# Small_e-PaperShield_v2_1.net
KiCad netlist of a schematic drawn in EAGLE
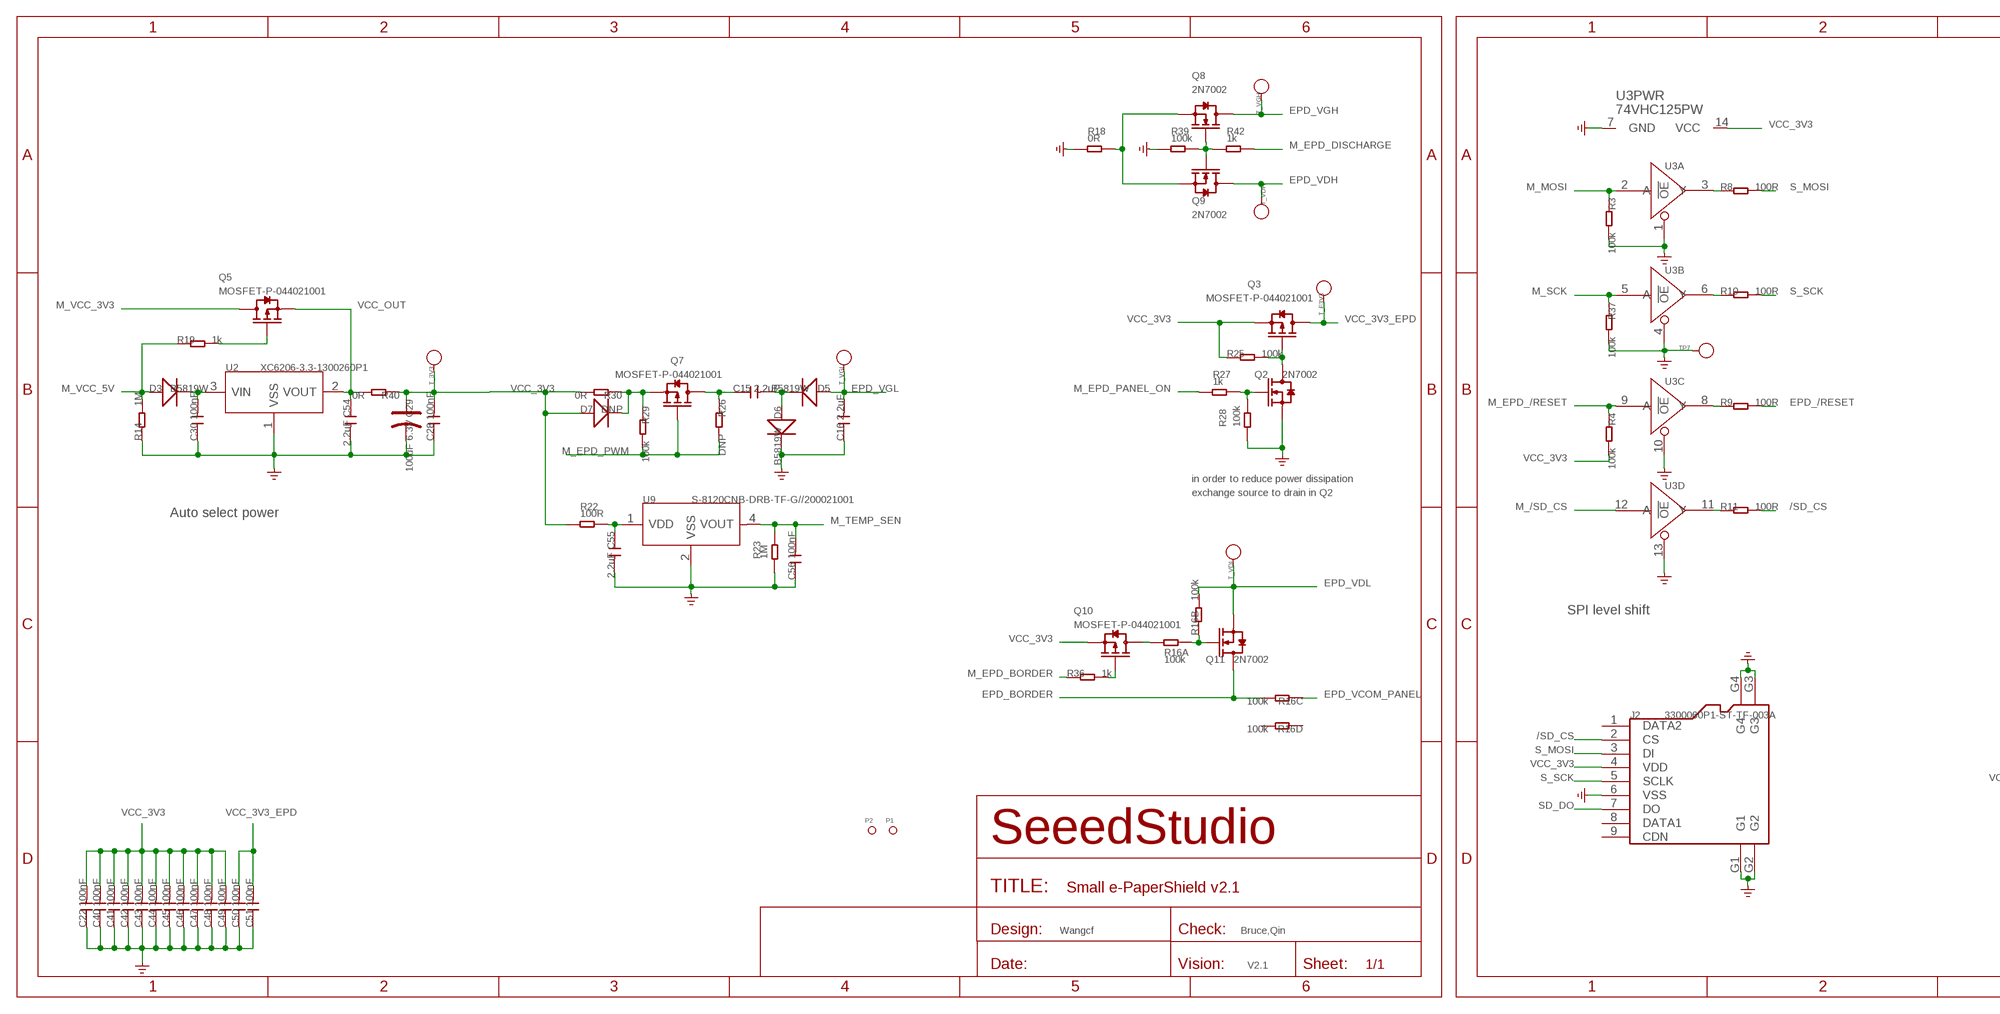
[diagram p0: schematic, sheet 1, part 1 of 2]
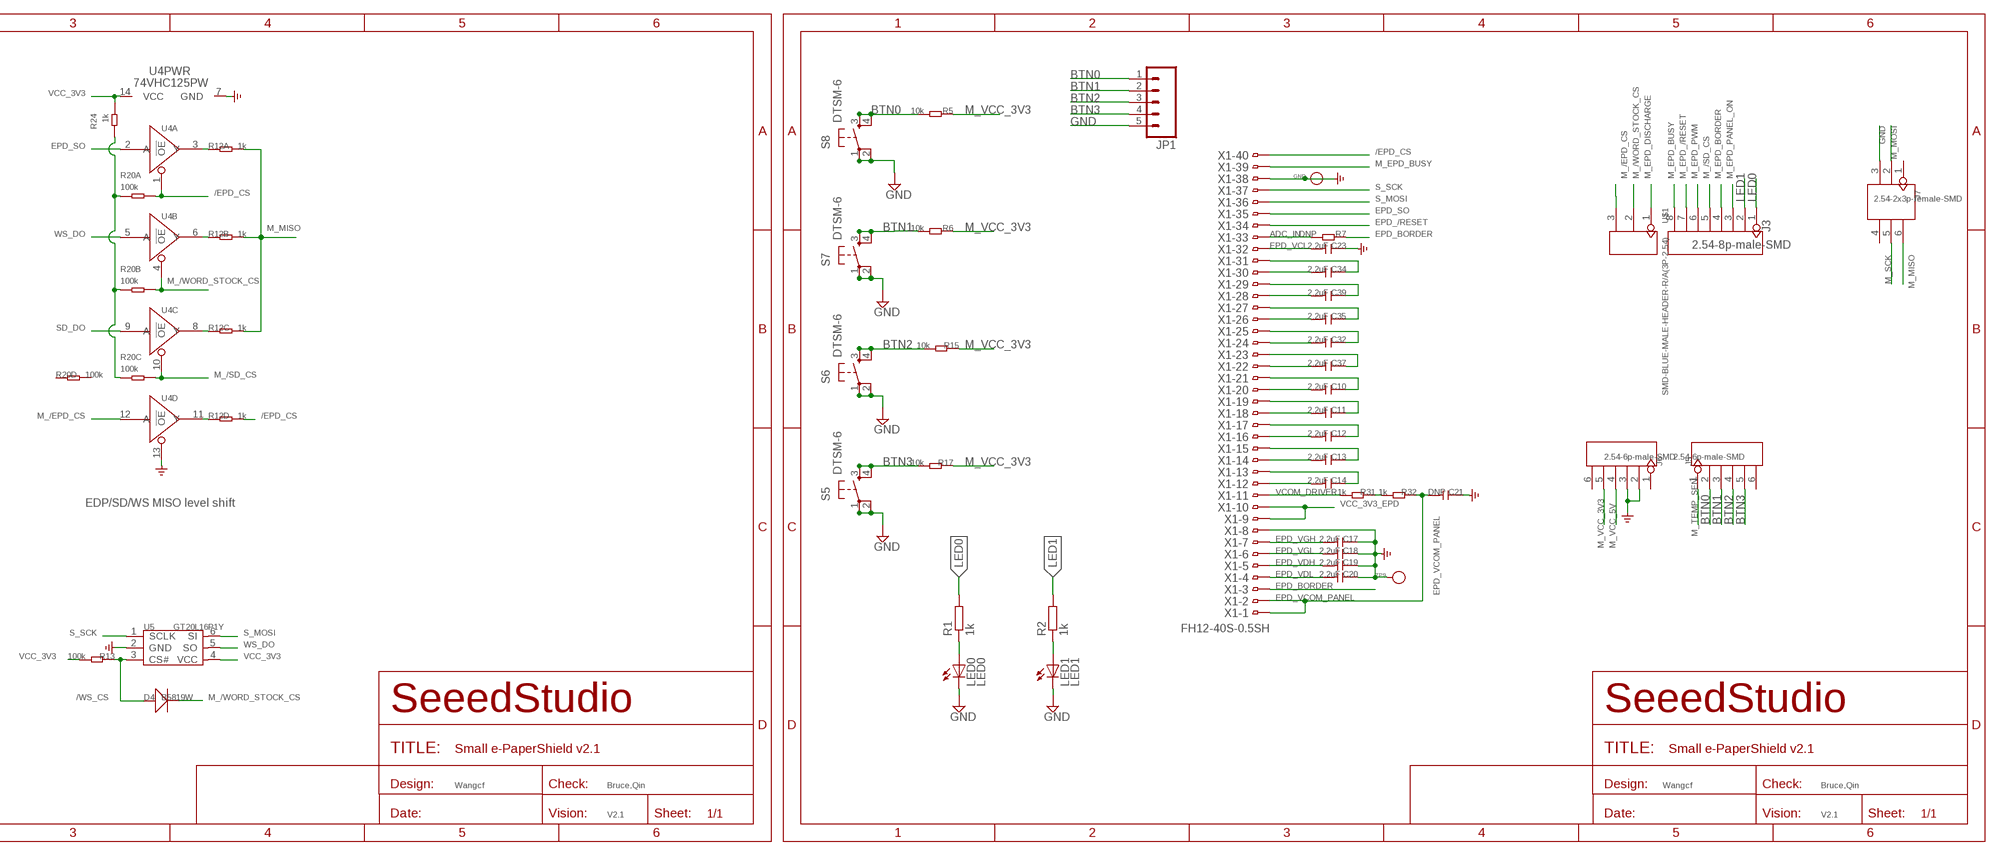
[diagram p1: schematic, sheet 1, part 2 of 2]

(export (version "E")
  (design (tool "Eeschema 10.0.6"))
  (components
    (comp (ref "C10")
      (value "2.2uF")
      (footprint "eagle-import:C0805")
      (libsource (lib "eagle-import") (part "C-0805"))
    )
    (comp (ref "C11")
      (value "2.2uF")
      (footprint "eagle-import:C0805")
      (libsource (lib "eagle-import") (part "C-0805"))
    )
    (comp (ref "C12")
      (value "2.2uF")
      (footprint "eagle-import:C0805")
      (libsource (lib "eagle-import") (part "C-0805"))
    )
    (comp (ref "C13")
      (value "2.2uF")
      (footprint "eagle-import:C0805")
      (libsource (lib "eagle-import") (part "C-0805"))
    )
    (comp (ref "C14")
      (value "2.2uF")
      (footprint "eagle-import:C0805")
      (libsource (lib "eagle-import") (part "C-0805"))
    )
    (comp (ref "C15")
      (value "2.2uF")
      (footprint "eagle-import:C0805")
      (libsource (lib "eagle-import") (part "C-0805"))
    )
    (comp (ref "C16")
      (value "2.2uF")
      (footprint "eagle-import:C0805")
      (libsource (lib "eagle-import") (part "C-0805"))
    )
    (comp (ref "C17")
      (value "2.2uF")
      (footprint "eagle-import:C0805")
      (libsource (lib "eagle-import") (part "C-0805"))
    )
    (comp (ref "C18")
      (value "2.2uF")
      (footprint "eagle-import:C0805")
      (libsource (lib "eagle-import") (part "C-0805"))
    )
    (comp (ref "C19")
      (value "2.2uF")
      (footprint "eagle-import:C0805")
      (libsource (lib "eagle-import") (part "C-0805"))
    )
    (comp (ref "C20")
      (value "2.2uF")
      (footprint "eagle-import:C0805")
      (libsource (lib "eagle-import") (part "C-0805"))
    )
    (comp (ref "C21")
      (value "DNP")
      (footprint "eagle-import:C0805")
      (libsource (lib "eagle-import") (part "C-0805"))
    )
    (comp (ref "C22")
      (value "100nF")
      (footprint "eagle-import:C0603")
      (libsource (lib "eagle-import") (part "C-0603"))
    )
    (comp (ref "C23")
      (value "2.2uF")
      (footprint "eagle-import:C0805")
      (libsource (lib "eagle-import") (part "C-0805"))
    )
    (comp (ref "C28")
      (value "100nF")
      (footprint "eagle-import:C0603")
      (libsource (lib "eagle-import") (part "C-0603"))
    )
    (comp (ref "C29")
      (value "100uF 6.3V")
      (footprint "eagle-import:AVX-B")
      (libsource (lib "eagle-import") (part "CAP-AVX-B"))
    )
    (comp (ref "C30")
      (value "100nF")
      (footprint "eagle-import:C0603")
      (libsource (lib "eagle-import") (part "C-0603"))
    )
    (comp (ref "C32")
      (value "2.2uF")
      (footprint "eagle-import:C0805")
      (libsource (lib "eagle-import") (part "C-0805"))
    )
    (comp (ref "C34")
      (value "2.2uF")
      (footprint "eagle-import:C0805")
      (libsource (lib "eagle-import") (part "C-0805"))
    )
    (comp (ref "C35")
      (value "2.2uF")
      (footprint "eagle-import:C0805")
      (libsource (lib "eagle-import") (part "C-0805"))
    )
    (comp (ref "C37")
      (value "2.2uF")
      (footprint "eagle-import:C0805")
      (libsource (lib "eagle-import") (part "C-0805"))
    )
    (comp (ref "C39")
      (value "2.2uF")
      (footprint "eagle-import:C0805")
      (libsource (lib "eagle-import") (part "C-0805"))
    )
    (comp (ref "C40")
      (value "100nF")
      (footprint "eagle-import:C0603")
      (libsource (lib "eagle-import") (part "C-0603"))
    )
    (comp (ref "C41")
      (value "100nF")
      (footprint "eagle-import:C0603")
      (libsource (lib "eagle-import") (part "C-0603"))
    )
    (comp (ref "C42")
      (value "100nF")
      (footprint "eagle-import:C0603")
      (libsource (lib "eagle-import") (part "C-0603"))
    )
    (comp (ref "C43")
      (value "100nF")
      (footprint "eagle-import:C0603")
      (libsource (lib "eagle-import") (part "C-0603"))
    )
    (comp (ref "C44")
      (value "100nF")
      (footprint "eagle-import:C0603")
      (libsource (lib "eagle-import") (part "C-0603"))
    )
    (comp (ref "C45")
      (value "100nF")
      (footprint "eagle-import:C0603")
      (libsource (lib "eagle-import") (part "C-0603"))
    )
    (comp (ref "C46")
      (value "100nF")
      (footprint "eagle-import:C0603")
      (libsource (lib "eagle-import") (part "C-0603"))
    )
    (comp (ref "C47")
      (value "100nF")
      (footprint "eagle-import:C0603")
      (libsource (lib "eagle-import") (part "C-0603"))
    )
    (comp (ref "C48")
      (value "100nF")
      (footprint "eagle-import:C0603")
      (libsource (lib "eagle-import") (part "C-0603"))
    )
    (comp (ref "C49")
      (value "100nF")
      (footprint "eagle-import:C0603")
      (libsource (lib "eagle-import") (part "C-0603"))
    )
    (comp (ref "C50")
      (value "100nF")
      (footprint "eagle-import:C0603")
      (libsource (lib "eagle-import") (part "C-0603"))
    )
    (comp (ref "C51")
      (value "100nF")
      (footprint "eagle-import:C0603")
      (libsource (lib "eagle-import") (part "C-0603"))
    )
    (comp (ref "C54")
      (value "2.2uF")
      (footprint "eagle-import:C0805")
      (libsource (lib "eagle-import") (part "C-0805"))
    )
    (comp (ref "C55")
      (value "2.2uF")
      (footprint "eagle-import:C0805")
      (libsource (lib "eagle-import") (part "C-0805"))
    )
    (comp (ref "C56")
      (value "100nF")
      (footprint "eagle-import:C0603")
      (libsource (lib "eagle-import") (part "C-0603"))
    )
    (comp (ref "D3")
      (value "B5819W")
      (footprint "eagle-import:SOD123")
      (libsource (lib "eagle-import") (part "D'1206'"))
    )
    (comp (ref "D4")
      (value "B5819W")
      (footprint "eagle-import:SOD123")
      (libsource (lib "eagle-import") (part "D'1206'"))
    )
    (comp (ref "D5")
      (value "B5819W")
      (footprint "eagle-import:SOD123")
      (libsource (lib "eagle-import") (part "D'1206'"))
    )
    (comp (ref "D6")
      (value "B5819W")
      (footprint "eagle-import:SOD123")
      (libsource (lib "eagle-import") (part "D'1206'"))
    )
    (comp (ref "D7")
      (value "DNP")
      (footprint "eagle-import:SOD123")
      (libsource (lib "eagle-import") (part "D'1206'"))
    )
    (comp (ref "GND")
      (value "PAD-TEST-POINT'3535'")
      (footprint "eagle-import:TP_3535")
      (fields (field (name "PARTNO") "DNP"))
      (libsource (lib "eagle-import") (part "PAD-TEST-POINT'3535'"))
    )
    (comp (ref "J2")
      (value "3300060P1-ST-TF-003A")
      (footprint "eagle-import:9P-SMD-W_-RING")
      (libsource (lib "eagle-import") (part "3300060P1-ST-TF-003A"))
    )
    (comp (ref "J3")
      (value "2.54-8p-male-SMD")
      (footprint "eagle-import:8P-2.54-SMD")
      (libsource (lib "eagle-import") (part "HEADER-8P-2.54-SMD"))
    )
    (comp (ref "J5")
      (value "2.54-6p-male-SMD")
      (footprint "eagle-import:6P-2.54-SMD")
      (libsource (lib "eagle-import") (part "HEADER-6P-SMD"))
    )
    (comp (ref "J6")
      (value "2.54-6p-male-SMD")
      (footprint "eagle-import:6P-2.54-SMD")
      (libsource (lib "eagle-import") (part "HEADER-6P-SMD"))
    )
    (comp (ref "J7")
      (value "2.54-2x3p-female-SMD")
      (footprint "eagle-import:2X3P-2.54-SMD")
      (libsource (lib "eagle-import") (part "HEADER-2X3P-SMD"))
    )
    (comp (ref "JP1")
      (value "M05PTH_LONGPADS")
      (footprint "eagle-import:1X05_LONGPADS")
      (libsource (lib "eagle-import") (part "M05PTH_LONGPADS"))
    )
    (comp (ref "LED0")
      (value "LED0")
      (footprint "eagle-import:CHIPLED_0603")
      (libsource (lib "eagle-import") (part "LEDCHIPLED_0603"))
    )
    (comp (ref "LED1")
      (value "LED1")
      (footprint "eagle-import:CHIPLED_0603")
      (libsource (lib "eagle-import") (part "LEDCHIPLED_0603"))
    )
    (comp (ref "P1")
      (value "PAD-MARK")
      (footprint "eagle-import:ROUND-MARK-1.0")
      (fields (field (name "PARTNO") "DNP"))
      (libsource (lib "eagle-import") (part "PAD-MARK"))
    )
    (comp (ref "P2")
      (value "PAD-MARK")
      (footprint "eagle-import:ROUND-MARK-1.0")
      (fields (field (name "PARTNO") "DNP"))
      (libsource (lib "eagle-import") (part "PAD-MARK"))
    )
    (comp (ref "Q2")
      (value "2N7002")
      (footprint "eagle-import:SOT23")
      (libsource (lib "eagle-import") (part "MOSFET-N'SOT23'"))
    )
    (comp (ref "Q3")
      (value "MOSFET-P-044021001")
      (footprint "eagle-import:SOT23")
      (libsource (lib "eagle-import") (part "MOSFET-P-044021001"))
    )
    (comp (ref "Q5")
      (value "MOSFET-P-044021001")
      (footprint "eagle-import:SOT23")
      (libsource (lib "eagle-import") (part "MOSFET-P-044021001"))
    )
    (comp (ref "Q7")
      (value "MOSFET-P-044021001")
      (footprint "eagle-import:SOT23")
      (libsource (lib "eagle-import") (part "MOSFET-P-044021001"))
    )
    (comp (ref "Q8")
      (value "2N7002")
      (footprint "eagle-import:SOT23")
      (libsource (lib "eagle-import") (part "MOSFET-N'SOT23'"))
    )
    (comp (ref "Q9")
      (value "2N7002")
      (footprint "eagle-import:SOT23")
      (libsource (lib "eagle-import") (part "MOSFET-N'SOT23'"))
    )
    (comp (ref "Q10")
      (value "MOSFET-P-044021001")
      (footprint "eagle-import:SOT23")
      (libsource (lib "eagle-import") (part "MOSFET-P-044021001"))
    )
    (comp (ref "Q11")
      (value "2N7002")
      (footprint "eagle-import:SOT23")
      (libsource (lib "eagle-import") (part "MOSFET-N'SOT23'"))
    )
    (comp (ref "R1")
      (value "1k")
      (footprint "eagle-import:R0603")
      (libsource (lib "eagle-import") (part "R-EU_R0603"))
    )
    (comp (ref "R2")
      (value "1k")
      (footprint "eagle-import:R0603")
      (libsource (lib "eagle-import") (part "R-EU_R0603"))
    )
    (comp (ref "R3")
      (value "100k")
      (footprint "eagle-import:R0603")
      (libsource (lib "eagle-import") (part "R-0603"))
    )
    (comp (ref "R4")
      (value "100k")
      (footprint "eagle-import:R0603")
      (libsource (lib "eagle-import") (part "R-0603"))
    )
    (comp (ref "R5")
      (value "10k")
      (footprint "eagle-import:R0603")
      (libsource (lib "eagle-import") (part "R-0603"))
    )
    (comp (ref "R6")
      (value "10k")
      (footprint "eagle-import:R0603")
      (libsource (lib "eagle-import") (part "R-0603"))
    )
    (comp (ref "R7")
      (value "DNP")
      (footprint "eagle-import:R0603")
      (libsource (lib "eagle-import") (part "R-0603"))
    )
    (comp (ref "R8")
      (value "100R")
      (footprint "eagle-import:R0603")
      (libsource (lib "eagle-import") (part "R-0603"))
    )
    (comp (ref "R9")
      (value "100R")
      (footprint "eagle-import:R0603")
      (libsource (lib "eagle-import") (part "R-0603"))
    )
    (comp (ref "R10")
      (value "100R")
      (footprint "eagle-import:R0603")
      (libsource (lib "eagle-import") (part "R-0603"))
    )
    (comp (ref "R11")
      (value "100R")
      (footprint "eagle-import:R0603")
      (libsource (lib "eagle-import") (part "R-0603"))
    )
    (comp (ref "R12")
      (value "1k")
      (footprint "eagle-import:1206-8-3.3X2.4")
      (libsource (lib "eagle-import") (part "R-4R-1206"))
    )
    (comp (ref "R13")
      (value "100k")
      (footprint "eagle-import:R0603")
      (libsource (lib "eagle-import") (part "R-0603"))
    )
    (comp (ref "R14")
      (value "1M")
      (footprint "eagle-import:R0603")
      (libsource (lib "eagle-import") (part "R-0603"))
    )
    (comp (ref "R15")
      (value "10k")
      (footprint "eagle-import:R0603")
      (libsource (lib "eagle-import") (part "R-0603"))
    )
    (comp (ref "R16")
      (value "100k")
      (footprint "eagle-import:1206-8-3.3X2.4")
      (libsource (lib "eagle-import") (part "R-4R-1206"))
    )
    (comp (ref "R17")
      (value "10k")
      (footprint "eagle-import:R0603")
      (libsource (lib "eagle-import") (part "R-0603"))
    )
    (comp (ref "R18")
      (value "0R")
      (footprint "eagle-import:R0603")
      (libsource (lib "eagle-import") (part "R-0603"))
    )
    (comp (ref "R19")
      (value "1k")
      (footprint "eagle-import:R0603")
      (libsource (lib "eagle-import") (part "R-0603"))
    )
    (comp (ref "R20")
      (value "100k")
      (footprint "eagle-import:1206-8-3.3X2.4")
      (libsource (lib "eagle-import") (part "R-4R-1206"))
    )
    (comp (ref "R22")
      (value "100R")
      (footprint "eagle-import:R0603")
      (libsource (lib "eagle-import") (part "R-0603"))
    )
    (comp (ref "R23")
      (value "1M")
      (footprint "eagle-import:R0603")
      (libsource (lib "eagle-import") (part "R-0603"))
    )
    (comp (ref "R24")
      (value "1k")
      (footprint "eagle-import:R0603")
      (libsource (lib "eagle-import") (part "R-0603"))
    )
    (comp (ref "R25")
      (value "100k")
      (footprint "eagle-import:R0603")
      (libsource (lib "eagle-import") (part "R-0603"))
    )
    (comp (ref "R26")
      (value "DNP")
      (footprint "eagle-import:R0603")
      (libsource (lib "eagle-import") (part "R-0603"))
    )
    (comp (ref "R27")
      (value "1k")
      (footprint "eagle-import:R0603")
      (libsource (lib "eagle-import") (part "R-0603"))
    )
    (comp (ref "R28")
      (value "100k")
      (footprint "eagle-import:R0603")
      (libsource (lib "eagle-import") (part "R-0603"))
    )
    (comp (ref "R29")
      (value "100k")
      (footprint "eagle-import:R0603")
      (libsource (lib "eagle-import") (part "R-0603"))
    )
    (comp (ref "R30")
      (value "0R")
      (footprint "eagle-import:R0603")
      (libsource (lib "eagle-import") (part "R-0603"))
    )
    (comp (ref "R31")
      (value "1k")
      (footprint "eagle-import:R0603")
      (libsource (lib "eagle-import") (part "R-0603"))
    )
    (comp (ref "R32")
      (value "1k")
      (footprint "eagle-import:R0603")
      (libsource (lib "eagle-import") (part "R-0603"))
    )
    (comp (ref "R36")
      (value "1k")
      (footprint "eagle-import:R0603")
      (libsource (lib "eagle-import") (part "R-0603"))
    )
    (comp (ref "R37")
      (value "100k")
      (footprint "eagle-import:R0603")
      (libsource (lib "eagle-import") (part "R-0603"))
    )
    (comp (ref "R39")
      (value "100k")
      (footprint "eagle-import:R0603")
      (libsource (lib "eagle-import") (part "R-0603"))
    )
    (comp (ref "R40")
      (value "0R")
      (footprint "eagle-import:R0603")
      (libsource (lib "eagle-import") (part "R-0603"))
    )
    (comp (ref "R42")
      (value "1k")
      (footprint "eagle-import:R0603")
      (libsource (lib "eagle-import") (part "R-0603"))
    )
    (comp (ref "S5")
      (value "DTSM-6")
      (footprint "eagle-import:DTSM-6")
      (libsource (lib "eagle-import") (part "DTSM-6"))
    )
    (comp (ref "S6")
      (value "DTSM-6")
      (footprint "eagle-import:DTSM-6")
      (libsource (lib "eagle-import") (part "DTSM-6"))
    )
    (comp (ref "S7")
      (value "DTSM-6")
      (footprint "eagle-import:DTSM-6")
      (libsource (lib "eagle-import") (part "DTSM-6"))
    )
    (comp (ref "S8")
      (value "DTSM-6")
      (footprint "eagle-import:DTSM-6")
      (libsource (lib "eagle-import") (part "DTSM-6"))
    )
    (comp (ref "TP7")
      (value "PAD-TEST-POINT'3535'")
      (footprint "eagle-import:TP_3535")
      (fields (field (name "PARTNO") "DNP"))
      (libsource (lib "eagle-import") (part "PAD-TEST-POINT'3535'"))
    )
    (comp (ref "TP9")
      (value "PAD-TEST-POINT'3535'")
      (footprint "eagle-import:TP_3535")
      (fields (field (name "PARTNO") "DNP"))
      (libsource (lib "eagle-import") (part "PAD-TEST-POINT'3535'"))
    )
    (comp (ref "T_3V3")
      (value "PAD-TEST-POINT'3535'")
      (footprint "eagle-import:TP_3535")
      (fields (field (name "PARTNO") "DNP"))
      (libsource (lib "eagle-import") (part "PAD-TEST-POINT'3535'"))
    )
    (comp (ref "T_E3V3")
      (value "PAD-TEST-POINT'3535'")
      (footprint "eagle-import:TP_3535")
      (fields (field (name "PARTNO") "DNP"))
      (libsource (lib "eagle-import") (part "PAD-TEST-POINT'3535'"))
    )
    (comp (ref "T_VDH")
      (value "PAD-TEST-POINT'3535'")
      (footprint "eagle-import:TP_3535")
      (fields (field (name "PARTNO") "DNP"))
      (libsource (lib "eagle-import") (part "PAD-TEST-POINT'3535'"))
    )
    (comp (ref "T_VDL")
      (value "PAD-TEST-POINT'3535'")
      (footprint "eagle-import:TP_3535")
      (fields (field (name "PARTNO") "DNP"))
      (libsource (lib "eagle-import") (part "PAD-TEST-POINT'3535'"))
    )
    (comp (ref "T_VGH")
      (value "PAD-TEST-POINT'3535'")
      (footprint "eagle-import:TP_3535")
      (fields (field (name "PARTNO") "DNP"))
      (libsource (lib "eagle-import") (part "PAD-TEST-POINT'3535'"))
    )
    (comp (ref "T_VGL")
      (value "PAD-TEST-POINT'3535'")
      (footprint "eagle-import:TP_3535")
      (fields (field (name "PARTNO") "DNP"))
      (libsource (lib "eagle-import") (part "PAD-TEST-POINT'3535'"))
    )
    (comp (ref "U$1")
      (value "SMD-BLUE-MALE-HEADER-R/A(3P-2.54)")
      (footprint "eagle-import:H3-SMD-2.54")
      (libsource (lib "eagle-import") (part "SMD-BLUE-MALE-HEADER-R/A(3P-2.54)"))
    )
    (comp (ref "U2")
      (value "XC6206-3.3-1300260P1")
      (footprint "eagle-import:SOT23")
      (libsource (lib "eagle-import") (part "XC6206-3.3-1300260P1"))
    )
    (comp (ref "U3")
      (value "74VHC125PW")
      (footprint "eagle-import:TSSOP14")
      (libsource (lib "eagle-import") (part "74V125PWHC"))
    )
    (comp (ref "U4")
      (value "74VHC125PW")
      (footprint "eagle-import:TSSOP14")
      (libsource (lib "eagle-import") (part "74V125PWHC"))
    )
    (comp (ref "U5")
      (value "GT20L16P1Y")
      (footprint "eagle-import:SOT23-6")
      (libsource (lib "eagle-import") (part "GT20L16P1Y"))
    )
    (comp (ref "U9")
      (value "S-8120CNB-DRB-TF-G//200021001")
      (footprint "eagle-import:SC-82AB")
      (libsource (lib "eagle-import") (part "S-8110C/8120C"))
    )
    (comp (ref "X1")
      (value "FH12-40S-0.5SH")
      (footprint "eagle-import:FH12-40S-0.5SH")
      (fields (field (name "MPN") "FH12-40S-0.5SH(55)"))
      (libsource (lib "eagle-import") (part "FH12-40S-0.5SH"))
    )
  )
  (nets
    (net (code "1") (name "/ADC_IN") (class "Default")
      (node (ref "R7") (pin "2") (pinfunction "2_2") (pintype "passive"))
      (node (ref "X1") (pin "33") (pinfunction "1_33") (pintype "passive"))
    )
    (net (code "2") (name "/BTN0") (class "Default")
      (node (ref "J5") (pin "2") (pinfunction "2_2") (pintype "bidirectional"))
      (node (ref "JP1") (pin "1") (pinfunction "1_1") (pintype "passive"))
      (node (ref "R5") (pin "2") (pinfunction "2_2") (pintype "passive"))
      (node (ref "S8") (pin "3") (pinfunction "3_3") (pintype "passive"))
      (node (ref "S8") (pin "4") (pinfunction "4_4") (pintype "passive"))
    )
    (net (code "3") (name "/BTN1") (class "Default")
      (node (ref "J5") (pin "3") (pinfunction "3_3") (pintype "bidirectional"))
      (node (ref "JP1") (pin "2") (pinfunction "2_2") (pintype "passive"))
      (node (ref "R6") (pin "2") (pinfunction "2_2") (pintype "passive"))
      (node (ref "S7") (pin "3") (pinfunction "3_3") (pintype "passive"))
      (node (ref "S7") (pin "4") (pinfunction "4_4") (pintype "passive"))
    )
    (net (code "4") (name "/BTN2") (class "Default")
      (node (ref "J5") (pin "4") (pinfunction "4_4") (pintype "bidirectional"))
      (node (ref "JP1") (pin "3") (pinfunction "3_3") (pintype "passive"))
      (node (ref "R15") (pin "2") (pinfunction "2_2") (pintype "passive"))
      (node (ref "S6") (pin "3") (pinfunction "3_3") (pintype "passive"))
      (node (ref "S6") (pin "4") (pinfunction "4_4") (pintype "passive"))
    )
    (net (code "5") (name "/BTN3") (class "Default")
      (node (ref "J5") (pin "5") (pinfunction "5_5") (pintype "bidirectional"))
      (node (ref "JP1") (pin "4") (pinfunction "4_4") (pintype "passive"))
      (node (ref "R17") (pin "2") (pinfunction "2_2") (pintype "passive"))
      (node (ref "S5") (pin "3") (pinfunction "3_3") (pintype "passive"))
      (node (ref "S5") (pin "4") (pinfunction "4_4") (pintype "passive"))
    )
    (net (code "6") (name "/EPD_BORDER") (class "Default")
      (node (ref "Q11") (pin "3") (pinfunction "D_3") (pintype "passive"))
      (node (ref "R16") (pin "6") (pinfunction "2_6") (pintype "passive"))
      (node (ref "R7") (pin "1") (pinfunction "1_1") (pintype "passive"))
      (node (ref "X1") (pin "3") (pinfunction "1_3") (pintype "passive"))
    )
    (net (code "7") (name "/EPD_SO") (class "Default")
      (node (ref "U4") (pin "2") (pinfunction "A_2") (pintype "bidirectional"))
      (node (ref "X1") (pin "35") (pinfunction "1_35") (pintype "passive"))
    )
    (net (code "8") (name "/EPD_VCL") (class "Default")
      (node (ref "C23") (pin "2") (pinfunction "2_2") (pintype "passive"))
      (node (ref "X1") (pin "32") (pinfunction "1_32") (pintype "passive"))
    )
    (net (code "9") (name "/EPD_VCOM_PANEL") (class "Default")
      (node (ref "C21") (pin "2") (pinfunction "2_2") (pintype "passive"))
      (node (ref "R16") (pin "3") (pinfunction "1_3") (pintype "passive"))
      (node (ref "R32") (pin "1") (pinfunction "1_1") (pintype "passive"))
      (node (ref "X1") (pin "1") (pinfunction "1_1") (pintype "passive"))
      (node (ref "X1") (pin "2") (pinfunction "1_2") (pintype "passive"))
    )
    (net (code "10") (name "/EPD_VDH") (class "Default")
      (node (ref "C19") (pin "2") (pinfunction "2_2") (pintype "passive"))
      (node (ref "Q9") (pin "3") (pinfunction "D_3") (pintype "passive"))
      (node (ref "T_VDH") (pin "T") (pinfunction "T_T") (pintype "bidirectional"))
      (node (ref "X1") (pin "5") (pinfunction "1_5") (pintype "passive"))
    )
    (net (code "11") (name "/EPD_VDL") (class "Default")
      (node (ref "C20") (pin "2") (pinfunction "2_2") (pintype "passive"))
      (node (ref "Q11") (pin "2") (pinfunction "S_2") (pintype "passive"))
      (node (ref "R16") (pin "7") (pinfunction "2_7") (pintype "passive"))
      (node (ref "T_VDL") (pin "T") (pinfunction "T_T") (pintype "bidirectional"))
      (node (ref "X1") (pin "4") (pinfunction "1_4") (pintype "passive"))
    )
    (net (code "12") (name "/EPD_VGH") (class "Default")
      (node (ref "C17") (pin "2") (pinfunction "2_2") (pintype "passive"))
      (node (ref "Q8") (pin "3") (pinfunction "D_3") (pintype "passive"))
      (node (ref "T_VGH") (pin "T") (pinfunction "T_T") (pintype "bidirectional"))
      (node (ref "X1") (pin "7") (pinfunction "1_7") (pintype "passive"))
    )
    (net (code "13") (name "/EPD_VGL") (class "Default")
      (node (ref "C16") (pin "2") (pinfunction "2_2") (pintype "passive"))
      (node (ref "C18") (pin "2") (pinfunction "2_2") (pintype "passive"))
      (node (ref "D5") (pin "+") (pinfunction "+_+") (pintype "passive"))
      (node (ref "T_VGL") (pin "T") (pinfunction "T_T") (pintype "bidirectional"))
      (node (ref "X1") (pin "6") (pinfunction "1_6") (pintype "passive"))
    )
    (net (code "14") (name "/EPD_{slash}RESET") (class "Default")
      (node (ref "R9") (pin "2") (pinfunction "2_2") (pintype "passive"))
      (node (ref "X1") (pin "34") (pinfunction "1_34") (pintype "passive"))
    )
    (net (code "15") (name "/M_EPD_BORDER") (class "Default")
      (node (ref "J3") (pin "4") (pinfunction "4_4") (pintype "bidirectional"))
      (node (ref "R36") (pin "1") (pinfunction "1_1") (pintype "passive"))
    )
    (net (code "16") (name "/M_EPD_BUSY") (class "Default")
      (node (ref "J3") (pin "8") (pinfunction "8_8") (pintype "bidirectional"))
      (node (ref "X1") (pin "39") (pinfunction "1_39") (pintype "passive"))
    )
    (net (code "17") (name "/M_EPD_DISCHARGE") (class "Default")
      (node (ref "R42") (pin "2") (pinfunction "2_2") (pintype "passive"))
      (node (ref "U$1") (pin "1") (pinfunction "P$1_1") (pintype "bidirectional"))
    )
    (net (code "18") (name "/M_EPD_PANEL_ON") (class "Default")
      (node (ref "J3") (pin "3") (pinfunction "3_3") (pintype "bidirectional"))
      (node (ref "R27") (pin "1") (pinfunction "1_1") (pintype "passive"))
    )
    (net (code "19") (name "/M_EPD_PWM") (class "Default")
      (node (ref "J3") (pin "6") (pinfunction "6_6") (pintype "bidirectional"))
      (node (ref "Q7") (pin "1") (pinfunction "G_1") (pintype "passive"))
      (node (ref "R26") (pin "2") (pinfunction "2_2") (pintype "passive"))
      (node (ref "R29") (pin "2") (pinfunction "2_2") (pintype "passive"))
    )
    (net (code "20") (name "/M_EPD_{slash}RESET") (class "Default")
      (node (ref "J3") (pin "7") (pinfunction "7_7") (pintype "bidirectional"))
      (node (ref "R4") (pin "1") (pinfunction "1_1") (pintype "passive"))
      (node (ref "U3") (pin "9") (pinfunction "A_9") (pintype "bidirectional"))
    )
    (net (code "21") (name "/M_MISO") (class "Default")
      (node (ref "J7") (pin "6") (pinfunction "6_6") (pintype "bidirectional"))
      (node (ref "R12") (pin "6") (pinfunction "2_6") (pintype "passive"))
      (node (ref "R12") (pin "7") (pinfunction "2_7") (pintype "passive"))
      (node (ref "R12") (pin "8") (pinfunction "2_8") (pintype "passive"))
    )
    (net (code "22") (name "/M_MOSI") (class "Default")
      (node (ref "J7") (pin "2") (pinfunction "2_2") (pintype "bidirectional"))
      (node (ref "R3") (pin "1") (pinfunction "1_1") (pintype "passive"))
      (node (ref "U3") (pin "2") (pinfunction "A_2") (pintype "bidirectional"))
    )
    (net (code "23") (name "/M_SCK") (class "Default")
      (node (ref "J7") (pin "5") (pinfunction "5_5") (pintype "bidirectional"))
      (node (ref "R37") (pin "1") (pinfunction "1_1") (pintype "passive"))
      (node (ref "U3") (pin "5") (pinfunction "A_5") (pintype "bidirectional"))
    )
    (net (code "24") (name "/M_TEMP_SEN") (class "Default")
      (node (ref "C56") (pin "2") (pinfunction "2_2") (pintype "passive"))
      (node (ref "J5") (pin "1") (pinfunction "1_1") (pintype "bidirectional"))
      (node (ref "R23") (pin "2") (pinfunction "2_2") (pintype "passive"))
      (node (ref "U9") (pin "4") (pinfunction "VOUT_4") (pintype "output"))
    )
    (net (code "25") (name "/M_VCC_3V3") (class "Default")
      (node (ref "J6") (pin "5") (pinfunction "5_5") (pintype "bidirectional"))
      (node (ref "Q5") (pin "3") (pinfunction "D_3") (pintype "passive"))
      (node (ref "R15") (pin "1") (pinfunction "1_1") (pintype "passive"))
      (node (ref "R17") (pin "1") (pinfunction "1_1") (pintype "passive"))
      (node (ref "R5") (pin "1") (pinfunction "1_1") (pintype "passive"))
      (node (ref "R6") (pin "1") (pinfunction "1_1") (pintype "passive"))
    )
    (net (code "26") (name "/M_VCC_5V") (class "Default")
      (node (ref "D3") (pin "+") (pinfunction "+_+") (pintype "passive"))
      (node (ref "J6") (pin "4") (pinfunction "4_4") (pintype "bidirectional"))
      (node (ref "R14") (pin "2") (pinfunction "2_2") (pintype "passive"))
      (node (ref "R19") (pin "1") (pinfunction "1_1") (pintype "passive"))
    )
    (net (code "27") (name "/M_{slash}EPD_CS") (class "Default")
      (node (ref "U$1") (pin "3") (pinfunction "P$3_3") (pintype "bidirectional"))
      (node (ref "U4") (pin "12") (pinfunction "A_12") (pintype "bidirectional"))
    )
    (net (code "28") (name "/M_{slash}SD_CS") (class "Default")
      (node (ref "J3") (pin "5") (pinfunction "5_5") (pintype "bidirectional"))
      (node (ref "R20") (pin "6") (pinfunction "2_6") (pintype "passive"))
      (node (ref "U3") (pin "12") (pinfunction "A_12") (pintype "bidirectional"))
      (node (ref "U4") (pin "10") (pinfunction "~{OE}_10") (pintype "bidirectional"))
    )
    (net (code "29") (name "/M_{slash}WORD_STOCK_CS") (class "Default")
      (node (ref "D4") (pin "-") (pinfunction "-_-") (pintype "passive"))
      (node (ref "R20") (pin "7") (pinfunction "2_7") (pintype "passive"))
      (node (ref "U$1") (pin "2") (pinfunction "P$2_2") (pintype "bidirectional"))
      (node (ref "U4") (pin "4") (pinfunction "~{OE}_4") (pintype "bidirectional"))
    )
    (net (code "30") (name "/SD_DO") (class "Default")
      (node (ref "J2") (pin "7") (pinfunction "DO_7") (pintype "bidirectional"))
      (node (ref "U4") (pin "9") (pinfunction "A_9") (pintype "bidirectional"))
    )
    (net (code "31") (name "/S_MOSI") (class "Default")
      (node (ref "J2") (pin "3") (pinfunction "DI_3") (pintype "bidirectional"))
      (node (ref "R8") (pin "2") (pinfunction "2_2") (pintype "passive"))
      (node (ref "U5") (pin "6") (pinfunction "SI_6") (pintype "input"))
      (node (ref "X1") (pin "36") (pinfunction "1_36") (pintype "passive"))
    )
    (net (code "32") (name "/S_SCK") (class "Default")
      (node (ref "J2") (pin "5") (pinfunction "SCLK_5") (pintype "bidirectional"))
      (node (ref "R10") (pin "2") (pinfunction "2_2") (pintype "passive"))
      (node (ref "U5") (pin "1") (pinfunction "SCLK_1") (pintype "input"))
      (node (ref "X1") (pin "37") (pinfunction "1_37") (pintype "passive"))
    )
    (net (code "33") (name "/VCC_3V3") (class "Default")
      (node (ref "C22") (pin "2") (pinfunction "2_2") (pintype "passive"))
      (node (ref "C28") (pin "2") (pinfunction "2_2") (pintype "passive"))
      (node (ref "C29") (pin "+") (pinfunction "+_+") (pintype "passive"))
      (node (ref "C40") (pin "2") (pinfunction "2_2") (pintype "passive"))
      (node (ref "C41") (pin "2") (pinfunction "2_2") (pintype "passive"))
      (node (ref "C42") (pin "2") (pinfunction "2_2") (pintype "passive"))
      (node (ref "C43") (pin "2") (pinfunction "2_2") (pintype "passive"))
      (node (ref "C44") (pin "2") (pinfunction "2_2") (pintype "passive"))
      (node (ref "C45") (pin "2") (pinfunction "2_2") (pintype "passive"))
      (node (ref "C46") (pin "2") (pinfunction "2_2") (pintype "passive"))
      (node (ref "C47") (pin "2") (pinfunction "2_2") (pintype "passive"))
      (node (ref "C48") (pin "2") (pinfunction "2_2") (pintype "passive"))
      (node (ref "C49") (pin "2") (pinfunction "2_2") (pintype "passive"))
      (node (ref "D7") (pin "+") (pinfunction "+_+") (pintype "passive"))
      (node (ref "J2") (pin "4") (pinfunction "VDD_4") (pintype "bidirectional"))
      (node (ref "Q10") (pin "2") (pinfunction "S_2") (pintype "passive"))
      (node (ref "Q3") (pin "2") (pinfunction "S_2") (pintype "passive"))
      (node (ref "R13") (pin "2") (pinfunction "2_2") (pintype "passive"))
      (node (ref "R22") (pin "1") (pinfunction "1_1") (pintype "passive"))
      (node (ref "R24") (pin "1") (pinfunction "1_1") (pintype "passive"))
      (node (ref "R25") (pin "1") (pinfunction "1_1") (pintype "passive"))
      (node (ref "R30") (pin "2") (pinfunction "2_2") (pintype "passive"))
      (node (ref "R4") (pin "2") (pinfunction "2_2") (pintype "passive"))
      (node (ref "R40") (pin "1") (pinfunction "1_1") (pintype "passive"))
      (node (ref "T_3V3") (pin "T") (pinfunction "T_T") (pintype "bidirectional"))
      (node (ref "U3") (pin "14") (pinfunction "VCC_14") (pintype "power_in"))
      (node (ref "U4") (pin "14") (pinfunction "VCC_14") (pintype "power_in"))
      (node (ref "U5") (pin "4") (pinfunction "VCC_4") (pintype "power_in"))
    )
    (net (code "34") (name "/VCC_3V3_EPD") (class "Default")
      (node (ref "C50") (pin "2") (pinfunction "2_2") (pintype "passive"))
      (node (ref "C51") (pin "2") (pinfunction "2_2") (pintype "passive"))
      (node (ref "Q3") (pin "3") (pinfunction "D_3") (pintype "passive"))
      (node (ref "T_E3V3") (pin "T") (pinfunction "T_T") (pintype "bidirectional"))
      (node (ref "X1") (pin "10") (pinfunction "1_10") (pintype "passive"))
      (node (ref "X1") (pin "9") (pinfunction "1_9") (pintype "passive"))
    )
    (net (code "35") (name "/VCC_OUT") (class "Default")
      (node (ref "C54") (pin "1") (pinfunction "1_1") (pintype "passive"))
      (node (ref "Q5") (pin "2") (pinfunction "S_2") (pintype "passive"))
      (node (ref "R40") (pin "2") (pinfunction "2_2") (pintype "passive"))
      (node (ref "U2") (pin "2") (pinfunction "VOUT_2") (pintype "output"))
    )
    (net (code "36") (name "/VCOM_DRIVER") (class "Default")
      (node (ref "R31") (pin "2") (pinfunction "2_2") (pintype "passive"))
      (node (ref "X1") (pin "11") (pinfunction "1_11") (pintype "passive"))
    )
    (net (code "37") (name "/WS_DO") (class "Default")
      (node (ref "U4") (pin "5") (pinfunction "A_5") (pintype "bidirectional"))
      (node (ref "U5") (pin "5") (pinfunction "SO_5") (pintype "output"))
    )
    (net (code "38") (name "/{slash}EPD_CS") (class "Default")
      (node (ref "R12") (pin "5") (pinfunction "2_5") (pintype "passive"))
      (node (ref "R20") (pin "8") (pinfunction "2_8") (pintype "passive"))
      (node (ref "U4") (pin "1") (pinfunction "~{OE}_1") (pintype "bidirectional"))
      (node (ref "X1") (pin "40") (pinfunction "1_40") (pintype "passive"))
    )
    (net (code "39") (name "/{slash}SD_CS") (class "Default")
      (node (ref "J2") (pin "2") (pinfunction "CS_2") (pintype "bidirectional"))
      (node (ref "R11") (pin "2") (pinfunction "2_2") (pintype "passive"))
    )
    (net (code "40") (name "/{slash}WS_CS") (class "Default")
      (node (ref "D4") (pin "+") (pinfunction "+_+") (pintype "passive"))
      (node (ref "R13") (pin "1") (pinfunction "1_1") (pintype "passive"))
      (node (ref "U5") (pin "3") (pinfunction "CS#_3") (pintype "input"))
    )
    (net (code "41") (name "GND") (class "Default")
      (node (ref "C16") (pin "1") (pinfunction "1_1") (pintype "passive"))
      (node (ref "C17") (pin "1") (pinfunction "1_1") (pintype "passive"))
      (node (ref "C18") (pin "1") (pinfunction "1_1") (pintype "passive"))
      (node (ref "C19") (pin "1") (pinfunction "1_1") (pintype "passive"))
      (node (ref "C20") (pin "1") (pinfunction "1_1") (pintype "passive"))
      (node (ref "C21") (pin "1") (pinfunction "1_1") (pintype "passive"))
      (node (ref "C22") (pin "1") (pinfunction "1_1") (pintype "passive"))
      (node (ref "C23") (pin "1") (pinfunction "1_1") (pintype "passive"))
      (node (ref "C28") (pin "1") (pinfunction "1_1") (pintype "passive"))
      (node (ref "C29") (pin "-") (pinfunction "-_-") (pintype "passive"))
      (node (ref "C30") (pin "1") (pinfunction "1_1") (pintype "passive"))
      (node (ref "C40") (pin "1") (pinfunction "1_1") (pintype "passive"))
      (node (ref "C41") (pin "1") (pinfunction "1_1") (pintype "passive"))
      (node (ref "C42") (pin "1") (pinfunction "1_1") (pintype "passive"))
      (node (ref "C43") (pin "1") (pinfunction "1_1") (pintype "passive"))
      (node (ref "C44") (pin "1") (pinfunction "1_1") (pintype "passive"))
      (node (ref "C45") (pin "1") (pinfunction "1_1") (pintype "passive"))
      (node (ref "C46") (pin "1") (pinfunction "1_1") (pintype "passive"))
      (node (ref "C47") (pin "1") (pinfunction "1_1") (pintype "passive"))
      (node (ref "C48") (pin "1") (pinfunction "1_1") (pintype "passive"))
      (node (ref "C49") (pin "1") (pinfunction "1_1") (pintype "passive"))
      (node (ref "C50") (pin "1") (pinfunction "1_1") (pintype "passive"))
      (node (ref "C51") (pin "1") (pinfunction "1_1") (pintype "passive"))
      (node (ref "C54") (pin "2") (pinfunction "2_2") (pintype "passive"))
      (node (ref "C55") (pin "2") (pinfunction "2_2") (pintype "passive"))
      (node (ref "C56") (pin "1") (pinfunction "1_1") (pintype "passive"))
      (node (ref "D6") (pin "-") (pinfunction "-_-") (pintype "passive"))
      (node (ref "GND") (pin "T") (pinfunction "T_T") (pintype "bidirectional"))
      (node (ref "J2") (pin "6") (pinfunction "VSS_6") (pintype "bidirectional"))
      (node (ref "J2") (pin "G1") (pinfunction "G1_G1") (pintype "bidirectional"))
      (node (ref "J2") (pin "G2") (pinfunction "G2_G2") (pintype "bidirectional"))
      (node (ref "J2") (pin "G3") (pinfunction "G3_G3") (pintype "bidirectional"))
      (node (ref "J2") (pin "G4") (pinfunction "G4_G4") (pintype "bidirectional"))
      (node (ref "J6") (pin "2") (pinfunction "2_2") (pintype "bidirectional"))
      (node (ref "J6") (pin "3") (pinfunction "3_3") (pintype "bidirectional"))
      (node (ref "J7") (pin "3") (pinfunction "3_3") (pintype "bidirectional"))
      (node (ref "JP1") (pin "5") (pinfunction "5_5") (pintype "passive"))
      (node (ref "LED0") (pin "C") (pinfunction "C_C") (pintype "passive"))
      (node (ref "LED1") (pin "C") (pinfunction "C_C") (pintype "passive"))
      (node (ref "Q2") (pin "2") (pinfunction "S_2") (pintype "passive"))
      (node (ref "R14") (pin "1") (pinfunction "1_1") (pintype "passive"))
      (node (ref "R18") (pin "1") (pinfunction "1_1") (pintype "passive"))
      (node (ref "R23") (pin "1") (pinfunction "1_1") (pintype "passive"))
      (node (ref "R28") (pin "1") (pinfunction "1_1") (pintype "passive"))
      (node (ref "R3") (pin "2") (pinfunction "2_2") (pintype "passive"))
      (node (ref "R37") (pin "2") (pinfunction "2_2") (pintype "passive"))
      (node (ref "R39") (pin "1") (pinfunction "1_1") (pintype "passive"))
      (node (ref "S5") (pin "1") (pinfunction "1_1") (pintype "passive"))
      (node (ref "S5") (pin "2") (pinfunction "2_2") (pintype "passive"))
      (node (ref "S6") (pin "1") (pinfunction "1_1") (pintype "passive"))
      (node (ref "S6") (pin "2") (pinfunction "2_2") (pintype "passive"))
      (node (ref "S7") (pin "1") (pinfunction "1_1") (pintype "passive"))
      (node (ref "S7") (pin "2") (pinfunction "2_2") (pintype "passive"))
      (node (ref "S8") (pin "1") (pinfunction "1_1") (pintype "passive"))
      (node (ref "S8") (pin "2") (pinfunction "2_2") (pintype "passive"))
      (node (ref "TP7") (pin "T") (pinfunction "T_T") (pintype "bidirectional"))
      (node (ref "TP9") (pin "T") (pinfunction "T_T") (pintype "bidirectional"))
      (node (ref "U2") (pin "1") (pinfunction "VSS_1") (pintype "power_in"))
      (node (ref "U3") (pin "1") (pinfunction "~{OE}_1") (pintype "bidirectional"))
      (node (ref "U3") (pin "10") (pinfunction "~{OE}_10") (pintype "bidirectional"))
      (node (ref "U3") (pin "13") (pinfunction "~{OE}_13") (pintype "bidirectional"))
      (node (ref "U3") (pin "4") (pinfunction "~{OE}_4") (pintype "bidirectional"))
      (node (ref "U3") (pin "7") (pinfunction "GND_7") (pintype "power_in"))
      (node (ref "U4") (pin "13") (pinfunction "~{OE}_13") (pintype "bidirectional"))
      (node (ref "U4") (pin "7") (pinfunction "GND_7") (pintype "power_in"))
      (node (ref "U5") (pin "2") (pinfunction "GND_2") (pintype "power_in"))
      (node (ref "U9") (pin "2") (pinfunction "VSS_2") (pintype "power_in"))
      (node (ref "X1") (pin "38") (pinfunction "1_38") (pintype "passive"))
      (node (ref "X1") (pin "8") (pinfunction "1_8") (pintype "passive"))
    )
    (net (code "42") (name "LED0") (class "Default")
      (node (ref "J3") (pin "1") (pinfunction "1_1") (pintype "bidirectional"))
      (node (ref "R1") (pin "2") (pinfunction "2_2") (pintype "passive"))
    )
    (net (code "43") (name "LED1") (class "Default")
      (node (ref "J3") (pin "2") (pinfunction "2_2") (pintype "bidirectional"))
      (node (ref "R2") (pin "2") (pinfunction "2_2") (pintype "passive"))
    )
    (net (code "44") (name "Net-(C15-Pad2)") (class "Default")
      (node (ref "C15") (pin "2") (pinfunction "2_2") (pintype "passive"))
      (node (ref "D5") (pin "-") (pinfunction "-_-") (pintype "passive"))
      (node (ref "D6") (pin "+") (pinfunction "+_+") (pintype "passive"))
    )
    (net (code "45") (name "Net-(LED0-PadA)") (class "Default")
      (node (ref "LED0") (pin "A") (pinfunction "A_A") (pintype "passive"))
      (node (ref "R1") (pin "1") (pinfunction "1_1") (pintype "passive"))
    )
    (net (code "46") (name "Net-(LED1-PadA)") (class "Default")
      (node (ref "LED1") (pin "A") (pinfunction "A_A") (pintype "passive"))
      (node (ref "R2") (pin "1") (pinfunction "1_1") (pintype "passive"))
    )
    (net (code "47") (name "Net-(Q2-D)") (class "Default")
      (node (ref "Q2") (pin "3") (pinfunction "D_3") (pintype "passive"))
      (node (ref "Q3") (pin "1") (pinfunction "G_1") (pintype "passive"))
      (node (ref "R25") (pin "2") (pinfunction "2_2") (pintype "passive"))
    )
    (net (code "48") (name "Net-(Q2-G)") (class "Default")
      (node (ref "Q2") (pin "1") (pinfunction "G_1") (pintype "passive"))
      (node (ref "R27") (pin "2") (pinfunction "2_2") (pintype "passive"))
      (node (ref "R28") (pin "2") (pinfunction "2_2") (pintype "passive"))
    )
    (net (code "49") (name "Net-(Q5-G)") (class "Default")
      (node (ref "Q5") (pin "1") (pinfunction "G_1") (pintype "passive"))
      (node (ref "R19") (pin "2") (pinfunction "2_2") (pintype "passive"))
    )
    (net (code "50") (name "Net-(Q7-D)") (class "Default")
      (node (ref "C15") (pin "1") (pinfunction "1_1") (pintype "passive"))
      (node (ref "Q7") (pin "3") (pinfunction "D_3") (pintype "passive"))
      (node (ref "R26") (pin "1") (pinfunction "1_1") (pintype "passive"))
    )
    (net (code "51") (name "Net-(Q7-S)") (class "Default")
      (node (ref "D7") (pin "-") (pinfunction "-_-") (pintype "passive"))
      (node (ref "Q7") (pin "2") (pinfunction "S_2") (pintype "passive"))
      (node (ref "R29") (pin "1") (pinfunction "1_1") (pintype "passive"))
      (node (ref "R30") (pin "1") (pinfunction "1_1") (pintype "passive"))
    )
    (net (code "52") (name "Net-(Q8-G)") (class "Default")
      (node (ref "Q8") (pin "1") (pinfunction "G_1") (pintype "passive"))
      (node (ref "Q9") (pin "1") (pinfunction "G_1") (pintype "passive"))
      (node (ref "R39") (pin "2") (pinfunction "2_2") (pintype "passive"))
      (node (ref "R42") (pin "1") (pinfunction "1_1") (pintype "passive"))
    )
    (net (code "53") (name "Net-(Q8-S)") (class "Default")
      (node (ref "Q8") (pin "2") (pinfunction "S_2") (pintype "passive"))
      (node (ref "Q9") (pin "2") (pinfunction "S_2") (pintype "passive"))
      (node (ref "R18") (pin "2") (pinfunction "2_2") (pintype "passive"))
    )
    (net (code "54") (name "Net-(Q10-D)") (class "Default")
      (node (ref "Q10") (pin "3") (pinfunction "D_3") (pintype "passive"))
      (node (ref "R16") (pin "1") (pinfunction "1_1") (pintype "passive"))
    )
    (net (code "55") (name "Net-(Q10-G)") (class "Default")
      (node (ref "Q10") (pin "1") (pinfunction "G_1") (pintype "passive"))
      (node (ref "R36") (pin "2") (pinfunction "2_2") (pintype "passive"))
    )
    (net (code "56") (name "Net-(Q11-G)") (class "Default")
      (node (ref "Q11") (pin "1") (pinfunction "G_1") (pintype "passive"))
      (node (ref "R16") (pin "2") (pinfunction "1_2") (pintype "passive"))
      (node (ref "R16") (pin "8") (pinfunction "2_8") (pintype "passive"))
    )
    (net (code "57") (name "Net-(R12B-1)") (class "Default")
      (node (ref "R12") (pin "2") (pinfunction "1_2") (pintype "passive"))
      (node (ref "U4") (pin "6") (pinfunction "Y_6") (pintype "bidirectional"))
    )
    (net (code "58") (name "Net-(R12C-1)") (class "Default")
      (node (ref "R12") (pin "3") (pinfunction "1_3") (pintype "passive"))
      (node (ref "U4") (pin "8") (pinfunction "Y_8") (pintype "bidirectional"))
    )
    (net (code "59") (name "Net-(R12D-1)") (class "Default")
      (node (ref "R12") (pin "4") (pinfunction "1_4") (pintype "passive"))
      (node (ref "U4") (pin "11") (pinfunction "Y_11") (pintype "bidirectional"))
    )
    (net (code "60") (name "Net-(R20B-1)") (class "Default")
      (node (ref "R20") (pin "1") (pinfunction "1_1") (pintype "passive"))
      (node (ref "R20") (pin "2") (pinfunction "1_2") (pintype "passive"))
      (node (ref "R20") (pin "3") (pinfunction "1_3") (pintype "passive"))
      (node (ref "R24") (pin "2") (pinfunction "2_2") (pintype "passive"))
    )
    (net (code "61") (name "Net-(R31-Pad1)") (class "Default")
      (node (ref "R31") (pin "1") (pinfunction "1_1") (pintype "passive"))
      (node (ref "R32") (pin "2") (pinfunction "2_2") (pintype "passive"))
    )
    (net (code "62") (name "Net-(U2-VIN)") (class "Default")
      (node (ref "C30") (pin "2") (pinfunction "2_2") (pintype "passive"))
      (node (ref "D3") (pin "-") (pinfunction "-_-") (pintype "passive"))
      (node (ref "U2") (pin "3") (pinfunction "VIN_3") (pintype "input"))
    )
    (net (code "63") (name "Net-(U3A-Y)") (class "Default")
      (node (ref "R8") (pin "1") (pinfunction "1_1") (pintype "passive"))
      (node (ref "U3") (pin "3") (pinfunction "Y_3") (pintype "bidirectional"))
    )
    (net (code "64") (name "Net-(U3B-Y)") (class "Default")
      (node (ref "R10") (pin "1") (pinfunction "1_1") (pintype "passive"))
      (node (ref "U3") (pin "6") (pinfunction "Y_6") (pintype "bidirectional"))
    )
    (net (code "65") (name "Net-(U3C-Y)") (class "Default")
      (node (ref "R9") (pin "1") (pinfunction "1_1") (pintype "passive"))
      (node (ref "U3") (pin "8") (pinfunction "Y_8") (pintype "bidirectional"))
    )
    (net (code "66") (name "Net-(U3D-Y)") (class "Default")
      (node (ref "R11") (pin "1") (pinfunction "1_1") (pintype "passive"))
      (node (ref "U3") (pin "11") (pinfunction "Y_11") (pintype "bidirectional"))
    )
    (net (code "67") (name "Net-(U4A-Y)") (class "Default")
      (node (ref "R12") (pin "1") (pinfunction "1_1") (pintype "passive"))
      (node (ref "U4") (pin "3") (pinfunction "Y_3") (pintype "bidirectional"))
    )
    (net (code "68") (name "Net-(U9-VDD)") (class "Default")
      (node (ref "C55") (pin "1") (pinfunction "1_1") (pintype "passive"))
      (node (ref "R22") (pin "2") (pinfunction "2_2") (pintype "passive"))
      (node (ref "U9") (pin "1") (pinfunction "VDD_1") (pintype "power_in"))
    )
    (net (code "69") (name "Net-(X1D-1)") (class "Default")
      (node (ref "C14") (pin "2") (pinfunction "2_2") (pintype "passive"))
      (node (ref "X1") (pin "12") (pinfunction "1_12") (pintype "passive"))
    )
    (net (code "70") (name "Net-(X1E-1)") (class "Default")
      (node (ref "C14") (pin "1") (pinfunction "1_1") (pintype "passive"))
      (node (ref "X1") (pin "13") (pinfunction "1_13") (pintype "passive"))
    )
    (net (code "71") (name "Net-(X1F-1)") (class "Default")
      (node (ref "C13") (pin "2") (pinfunction "2_2") (pintype "passive"))
      (node (ref "X1") (pin "14") (pinfunction "1_14") (pintype "passive"))
    )
    (net (code "72") (name "Net-(X1G-1)") (class "Default")
      (node (ref "C13") (pin "1") (pinfunction "1_1") (pintype "passive"))
      (node (ref "X1") (pin "15") (pinfunction "1_15") (pintype "passive"))
    )
    (net (code "73") (name "Net-(X1H-1)") (class "Default")
      (node (ref "C12") (pin "2") (pinfunction "2_2") (pintype "passive"))
      (node (ref "X1") (pin "16") (pinfunction "1_16") (pintype "passive"))
    )
    (net (code "74") (name "Net-(X1I-1)") (class "Default")
      (node (ref "C12") (pin "1") (pinfunction "1_1") (pintype "passive"))
      (node (ref "X1") (pin "17") (pinfunction "1_17") (pintype "passive"))
    )
    (net (code "75") (name "Net-(X1J-1)") (class "Default")
      (node (ref "C11") (pin "2") (pinfunction "2_2") (pintype "passive"))
      (node (ref "X1") (pin "18") (pinfunction "1_18") (pintype "passive"))
    )
    (net (code "76") (name "Net-(X1K-1)") (class "Default")
      (node (ref "C11") (pin "1") (pinfunction "1_1") (pintype "passive"))
      (node (ref "X1") (pin "19") (pinfunction "1_19") (pintype "passive"))
    )
    (net (code "77") (name "Net-(X1M-1)") (class "Default")
      (node (ref "C10") (pin "2") (pinfunction "2_2") (pintype "passive"))
      (node (ref "X1") (pin "20") (pinfunction "1_20") (pintype "passive"))
    )
    (net (code "78") (name "Net-(X1N-1)") (class "Default")
      (node (ref "C10") (pin "1") (pinfunction "1_1") (pintype "passive"))
      (node (ref "X1") (pin "21") (pinfunction "1_21") (pintype "passive"))
    )
    (net (code "79") (name "Net-(X1O-1)") (class "Default")
      (node (ref "C37") (pin "2") (pinfunction "2_2") (pintype "passive"))
      (node (ref "X1") (pin "22") (pinfunction "1_22") (pintype "passive"))
    )
    (net (code "80") (name "Net-(X1P-1)") (class "Default")
      (node (ref "C37") (pin "1") (pinfunction "1_1") (pintype "passive"))
      (node (ref "X1") (pin "23") (pinfunction "1_23") (pintype "passive"))
    )
    (net (code "81") (name "Net-(X1Q-1)") (class "Default")
      (node (ref "C32") (pin "2") (pinfunction "2_2") (pintype "passive"))
      (node (ref "X1") (pin "24") (pinfunction "1_24") (pintype "passive"))
    )
    (net (code "82") (name "Net-(X1R-1)") (class "Default")
      (node (ref "C32") (pin "1") (pinfunction "1_1") (pintype "passive"))
      (node (ref "X1") (pin "25") (pinfunction "1_25") (pintype "passive"))
    )
    (net (code "83") (name "Net-(X1S-1)") (class "Default")
      (node (ref "C35") (pin "2") (pinfunction "2_2") (pintype "passive"))
      (node (ref "X1") (pin "26") (pinfunction "1_26") (pintype "passive"))
    )
    (net (code "84") (name "Net-(X1T-1)") (class "Default")
      (node (ref "C35") (pin "1") (pinfunction "1_1") (pintype "passive"))
      (node (ref "X1") (pin "27") (pinfunction "1_27") (pintype "passive"))
    )
    (net (code "85") (name "Net-(X1U-1)") (class "Default")
      (node (ref "C39") (pin "2") (pinfunction "2_2") (pintype "passive"))
      (node (ref "X1") (pin "28") (pinfunction "1_28") (pintype "passive"))
    )
    (net (code "86") (name "Net-(X1V-1)") (class "Default")
      (node (ref "C39") (pin "1") (pinfunction "1_1") (pintype "passive"))
      (node (ref "X1") (pin "29") (pinfunction "1_29") (pintype "passive"))
    )
    (net (code "87") (name "Net-(X1X-1)") (class "Default")
      (node (ref "C34") (pin "2") (pinfunction "2_2") (pintype "passive"))
      (node (ref "X1") (pin "30") (pinfunction "1_30") (pintype "passive"))
    )
    (net (code "88") (name "Net-(X1Y-1)") (class "Default")
      (node (ref "C34") (pin "1") (pinfunction "1_1") (pintype "passive"))
      (node (ref "X1") (pin "31") (pinfunction "1_31") (pintype "passive"))
    )
    (net (code "89") (name "unconnected-(J2-CDN-Pad9)") (class "Default")
      (node (ref "J2") (pin "9") (pinfunction "CDN_9") (pintype "bidirectional"))
    )
    (net (code "90") (name "unconnected-(J2-DATA1-Pad8)") (class "Default")
      (node (ref "J2") (pin "8") (pinfunction "DATA1_8") (pintype "bidirectional"))
    )
    (net (code "91") (name "unconnected-(J2-DATA2-Pad1)") (class "Default")
      (node (ref "J2") (pin "1") (pinfunction "DATA2_1") (pintype "bidirectional"))
    )
    (net (code "92") (name "unconnected-(J5-Pad6)") (class "Default")
      (node (ref "J5") (pin "6") (pinfunction "6_6") (pintype "bidirectional"))
    )
    (net (code "93") (name "unconnected-(J6-Pad1)") (class "Default")
      (node (ref "J6") (pin "1") (pinfunction "1_1") (pintype "bidirectional"))
    )
    (net (code "94") (name "unconnected-(J6-Pad6)") (class "Default")
      (node (ref "J6") (pin "6") (pinfunction "6_6") (pintype "bidirectional"))
    )
    (net (code "95") (name "unconnected-(J7-Pad1)") (class "Default")
      (node (ref "J7") (pin "1") (pinfunction "1_1") (pintype "bidirectional"))
    )
    (net (code "96") (name "unconnected-(J7-Pad4)") (class "Default")
      (node (ref "J7") (pin "4") (pinfunction "4_4") (pintype "bidirectional"))
    )
    (net (code "97") (name "unconnected-(R16D-1-Pad4)") (class "Default")
      (node (ref "R16") (pin "4") (pinfunction "1_4") (pintype "passive"))
    )
    (net (code "98") (name "unconnected-(R16D-2-Pad5)") (class "Default")
      (node (ref "R16") (pin "5") (pinfunction "2_5") (pintype "passive"))
    )
    (net (code "99") (name "unconnected-(R20D-1-Pad4)") (class "Default")
      (node (ref "R20") (pin "4") (pinfunction "1_4") (pintype "passive"))
    )
    (net (code "100") (name "unconnected-(R20D-2-Pad5)") (class "Default")
      (node (ref "R20") (pin "5") (pinfunction "2_5") (pintype "passive"))
    )
  )
)
